# Sheet2.net
KiCad netlist of a schematic drawn in Altium Designer
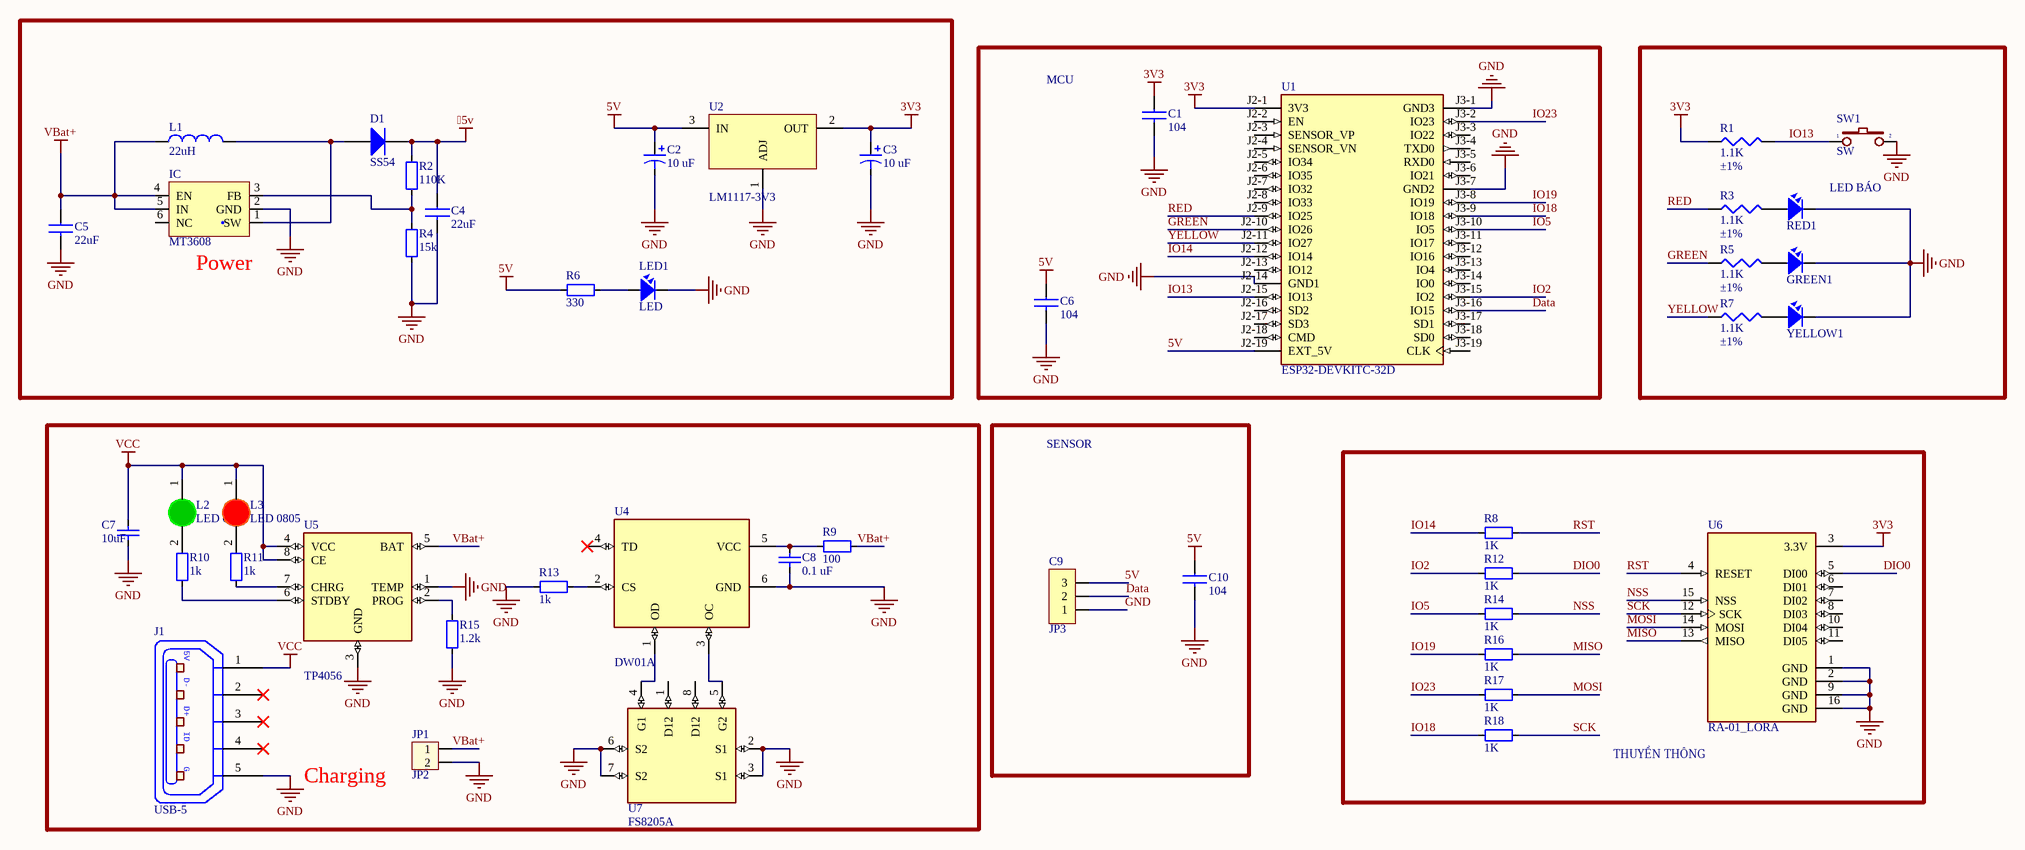
[diagram p0: Sheet2.SchDoc]

(export (version "E")
  (design (tool "Eeschema 10.0.6"))
  (components
    (comp (ref "C1")
      (value "104")
      (footprint "CAP0603")
      (description "CAP CER 30PF 50V NPO 0603")
      (fields
        (field (name "MANUFACTURER") "Yageo")
        (field (name "MANUFACTURER PART NUMBER") "CC0603JRNPO9BN300")
      )
      (libsource (lib "KhanhBK_SCH_Lib_6") (part "CC0603JRNPO9BN300"))
    )
    (comp (ref "C2")
      (value "10 uF")
      (footprint "C3MM")
      (description "Polarized Capacitor (Axial)")
      (fields (field (name "PUBLISHER") "Altium Limited"))
      (libsource (lib "My Library") (part "Cap Pol"))
    )
    (comp (ref "C3")
      (value "10 uF")
      (footprint "C3MM")
      (description "Polarized Capacitor (Axial)")
      (fields (field (name "PUBLISHER") "Altium Limited"))
      (libsource (lib "My Library") (part "Cap Pol"))
    )
    (comp (ref "C4")
      (value "22uF")
      (footprint "CAP0603")
      (description "CAP CER 30PF 50V NPO 0603")
      (fields
        (field (name "MANUFACTURER") "Yageo")
        (field (name "MANUFACTURER PART NUMBER") "CC0603JRNPO9BN300")
      )
      (libsource (lib "KhanhBK_SCH_Lib_6") (part "CC0603JRNPO9BN300"))
    )
    (comp (ref "C5")
      (value "22uF")
      (footprint "CAP0603")
      (description "CAP CER 30PF 50V NPO 0603")
      (fields
        (field (name "MANUFACTURER") "Yageo")
        (field (name "MANUFACTURER PART NUMBER") "CC0603JRNPO9BN300")
      )
      (libsource (lib "KhanhBK_SCH_Lib_6") (part "CC0603JRNPO9BN300"))
    )
    (comp (ref "C6")
      (value "104")
      (footprint "CAP0603")
      (description "CAP CER 30PF 50V NPO 0603")
      (fields
        (field (name "MANUFACTURER") "Yageo")
        (field (name "MANUFACTURER PART NUMBER") "CC0603JRNPO9BN300")
      )
      (libsource (lib "KhanhBK_SCH_Lib_6") (part "CC0603JRNPO9BN300"))
    )
    (comp (ref "C7")
      (value "10uF")
      (footprint "CAP_0805")
      (description "Capacitor")
      (fields (field (name "PUBLISHER") "Altium Limited"))
      (libsource (lib "My Library") (part "CapSMD"))
    )
    (comp (ref "C8")
      (value "0.1 uF")
      (footprint "CAP_0805")
      (description "Capacitor")
      (fields (field (name "PUBLISHER") "Altium Limited"))
      (libsource (lib "My Library") (part "CapSMD"))
    )
    (comp (ref "C9")
      (value "JP3")
      (footprint "JP3-C1T")
      (description "WR-PHD 2.54 mm Angled Socket Header")
      (fields
        (field (name "MANUFACTURER") "Würth Elektronik eiSos GmbH")
        (field (name "PARTNO") "613003143121")
        (field (name "CREATED BY") "Karrer Zheng")
      )
      (libsource (lib "KhanhBK_SCH_Library_1") (part "JP3"))
    )
    (comp (ref "C10")
      (value "104")
      (footprint "CAP0603")
      (description "CAP CER 30PF 50V NPO 0603")
      (fields
        (field (name "MANUFACTURER") "Yageo")
        (field (name "MANUFACTURER PART NUMBER") "CC0603JRNPO9BN300")
      )
      (libsource (lib "KhanhBK_SCH_Lib_6") (part "CC0603JRNPO9BN300"))
    )
    (comp (ref "D1")
      (value "SS54")
      (footprint "DIODE/POW/1A")
      (description "Diode Power")
      (fields (field (name "PUBLISHER") "Altium Limited"))
      (libsource (lib "Cty1") (part "Diode Power"))
    )
    (comp (ref "GREEN1")
      (value "LED")
      (footprint "LED-3MM-GREEN")
      (description "LED Single colour Green and Red")
      (libsource (lib "KhanhBK_SCH_Library_1") (part "LED"))
    )
    (comp (ref "IC") (value "MT3608") (footprint "TSOP 2") (libsource (lib "MT3608") (part "MT3608")))
    (comp (ref "J1")
      (value "USB-5")
      (footprint "USB-M1")
      (fields
        (field (name "MANUFACTURER") "FCI")
        (field (name "MANUFACTURER PART NUMBER") "10118193-0001LF")
        (field (name ".CREATOR") "MM")
        (field (name ".CHECKED PCB") "RF")
        (field (name ".CHECKED SCH") "MM")
      )
      (libsource (lib "My Library") (part "USB-5"))
    )
    (comp (ref "JP1")
      (value "JP2")
      (footprint "CON2")
      (description "Connector 2")
      (libsource (lib "My Library") (part "Con2"))
    )
    (comp (ref "L1")
      (value "22uH")
      (footprint "IND_400_500_212x114_SMD")
      (description "1mH Shielded Wirewound Inductor 600mA 1.82Ohm Max Nonstandard")
      (fields (field (name "MANUFACTURER") "Coilcraft") (field (name "MANUFACTURER PART NUMBER") "74477030"))
      (libsource (lib "Altium_Lib_by_KhueNguyenCreator") (part "IND_1mH-0.6A-20%-SMD"))
    )
    (comp (ref "L2")
      (value "LED 0805")
      (footprint "LED-0805-Green")
      (description "Dán")
      (libsource (lib "Altium_Lib_by_KhueNguyenCreator") (part "LED 0805 Xanh La"))
    )
    (comp (ref "L3")
      (value "LED 0805")
      (footprint "LED-0805-Red")
      (description "Dán")
      (libsource (lib "Altium_Lib_by_KhueNguyenCreator") (part "LED 0805 Do"))
    )
    (comp (ref "LED1")
      (value "LED")
      (footprint "LED-0805-Red")
      (description "LED Single colour Green and Red")
      (libsource (lib "My Library") (part "LED"))
    )
    (comp (ref "R1")
      (value "1.1K")
      (footprint "RES0603")
      (description "RES SMD 1K OHM 1% 1/10W 0603")
      (fields
        (field (name "MANUFACTURER") "Yageo")
        (field (name "MANUFACTURER PART NUMBER") "RT0603FRD071KL")
        (field (name "TOLERANCE") "±1%")
      )
      (libsource (lib "KhanhBK_SCH_Lib_6") (part "RT0603FRD071KL"))
    )
    (comp (ref "R2")
      (value "110K")
      (footprint "RES-SMD-0805")
      (description "Resistor")
      (fields
        (field (name "MANUFACTURER") "Generic Components")
        (field (name "PUBLISHER") "Altium Hobart Technology Centre")
      )
      (libsource (lib "My Library") (part "Resistor - SMD"))
    )
    (comp (ref "R3")
      (value "1.1K")
      (footprint "RES0603")
      (description "RES SMD 1K OHM 1% 1/10W 0603")
      (fields
        (field (name "MANUFACTURER") "Yageo")
        (field (name "MANUFACTURER PART NUMBER") "RT0603FRD071KL")
        (field (name "TOLERANCE") "±1%")
      )
      (libsource (lib "KhanhBK_SCH_Lib_6") (part "RT0603FRD071KL"))
    )
    (comp (ref "R4")
      (value "15k")
      (footprint "RES-SMD-0805")
      (description "Resistor")
      (fields
        (field (name "MANUFACTURER") "Generic Components")
        (field (name "PUBLISHER") "Altium Hobart Technology Centre")
      )
      (libsource (lib "My Library") (part "Resistor - SMD"))
    )
    (comp (ref "R5")
      (value "1.1K")
      (footprint "RES0603")
      (description "RES SMD 1K OHM 1% 1/10W 0603")
      (fields
        (field (name "MANUFACTURER") "Yageo")
        (field (name "MANUFACTURER PART NUMBER") "RT0603FRD071KL")
        (field (name "TOLERANCE") "±1%")
      )
      (libsource (lib "KhanhBK_SCH_Lib_6") (part "RT0603FRD071KL"))
    )
    (comp (ref "R6")
      (value "330")
      (footprint "RES-SMD-0805")
      (description "Resistor")
      (fields
        (field (name "MANUFACTURER") "Generic Components")
        (field (name "PUBLISHER") "Altium Hobart Technology Centre")
      )
      (libsource (lib "My Library") (part "Resistor - SMD"))
    )
    (comp (ref "R7")
      (value "1.1K")
      (footprint "RES0603")
      (description "RES SMD 1K OHM 1% 1/10W 0603")
      (fields
        (field (name "MANUFACTURER") "Yageo")
        (field (name "MANUFACTURER PART NUMBER") "RT0603FRD071KL")
        (field (name "TOLERANCE") "±1%")
      )
      (libsource (lib "KhanhBK_SCH_Lib_6") (part "RT0603FRD071KL"))
    )
    (comp (ref "R8")
      (value "1K")
      (footprint "RES-SMD-0805")
      (description "Resistor")
      (fields
        (field (name "MANUFACTURER") "Generic Components")
        (field (name "PUBLISHER") "Altium Hobart Technology Centre")
      )
      (libsource (lib "My Library") (part "Resistor - SMD"))
    )
    (comp (ref "R9")
      (value "100")
      (footprint "RES-SMD-0805")
      (description "Resistor")
      (fields
        (field (name "MANUFACTURER") "Generic Components")
        (field (name "PUBLISHER") "Altium Hobart Technology Centre")
      )
      (libsource (lib "My Library") (part "Resistor - SMD"))
    )
    (comp (ref "R10")
      (value "1k")
      (footprint "RES-SMD-0805")
      (description "Resistor")
      (fields
        (field (name "MANUFACTURER") "Generic Components")
        (field (name "PUBLISHER") "Altium Hobart Technology Centre")
      )
      (libsource (lib "My Library") (part "Resistor - SMD"))
    )
    (comp (ref "R11")
      (value "1k")
      (footprint "RES-SMD-0805")
      (description "Resistor")
      (fields
        (field (name "MANUFACTURER") "Generic Components")
        (field (name "PUBLISHER") "Altium Hobart Technology Centre")
      )
      (libsource (lib "My Library") (part "Resistor - SMD"))
    )
    (comp (ref "R12")
      (value "1K")
      (footprint "RES-SMD-0805")
      (description "Resistor")
      (fields
        (field (name "MANUFACTURER") "Generic Components")
        (field (name "PUBLISHER") "Altium Hobart Technology Centre")
      )
      (libsource (lib "My Library") (part "Resistor - SMD"))
    )
    (comp (ref "R13")
      (value "1k")
      (footprint "RES-SMD-0805")
      (description "Resistor")
      (fields
        (field (name "MANUFACTURER") "Generic Components")
        (field (name "PUBLISHER") "Altium Hobart Technology Centre")
      )
      (libsource (lib "My Library") (part "Resistor - SMD"))
    )
    (comp (ref "R14")
      (value "1K")
      (footprint "RES-SMD-0805")
      (description "Resistor")
      (fields
        (field (name "MANUFACTURER") "Generic Components")
        (field (name "PUBLISHER") "Altium Hobart Technology Centre")
      )
      (libsource (lib "My Library") (part "Resistor - SMD"))
    )
    (comp (ref "R15")
      (value "1.2k")
      (footprint "RES-SMD-0805")
      (description "Resistor")
      (fields
        (field (name "MANUFACTURER") "Generic Components")
        (field (name "PUBLISHER") "Altium Hobart Technology Centre")
      )
      (libsource (lib "My Library") (part "Resistor - SMD"))
    )
    (comp (ref "R16")
      (value "1K")
      (footprint "RES-SMD-0805")
      (description "Resistor")
      (fields
        (field (name "MANUFACTURER") "Generic Components")
        (field (name "PUBLISHER") "Altium Hobart Technology Centre")
      )
      (libsource (lib "My Library") (part "Resistor - SMD"))
    )
    (comp (ref "R17")
      (value "1K")
      (footprint "RES-SMD-0805")
      (description "Resistor")
      (fields
        (field (name "MANUFACTURER") "Generic Components")
        (field (name "PUBLISHER") "Altium Hobart Technology Centre")
      )
      (libsource (lib "My Library") (part "Resistor - SMD"))
    )
    (comp (ref "R18")
      (value "1K")
      (footprint "RES-SMD-0805")
      (description "Resistor")
      (fields
        (field (name "MANUFACTURER") "Generic Components")
        (field (name "PUBLISHER") "Altium Hobart Technology Centre")
      )
      (libsource (lib "My Library") (part "Resistor - SMD"))
    )
    (comp (ref "RED1")
      (value "LED")
      (footprint "LED-3MM-RED")
      (description "LED Single colour Green and Red")
      (libsource (lib "KhanhBK_SCH_Library_1") (part "LED"))
    )
    (comp (ref "SW1")
      (value "SW")
      (footprint "SW1-SMD")
      (description "Switch button 2 pin")
      (libsource (lib "KhanhBK_SCH_Library_1") (part "SW2"))
    )
    (comp (ref "U1")
      (value "ESP32-DEVKITC-32D")
      (footprint "MODULE_ESP32-DEVKITC-32D")
      (description "WiFi Development Tools (802.11) ESP32 General Development Kit, ESP32-WROOM-32D on the board")
      (fields (field (name "MF") "Espressif Systems"))
      (libsource (lib "ESP32-DEVKITC-32D") (part "ESP32-DEVKITC-32D"))
    )
    (comp (ref "U2")
      (value "LM1117-3V3")
      (footprint "LM1117-SOP")
      (description "800mA Low-Dropout Linear Regulator")
      (fields (field (name "CREATOR") "Nguyen Ba Bien"))
      (libsource (lib "My Library") (part "LM1117-ADJ"))
    )
    (comp (ref "U4")
      (value "DW01A")
      (footprint "SOT23-6")
      (description "One Cell Lithium-ion/Polymer Battery Protection IC")
      (libsource (lib "My Library") (part "DW01A"))
    )
    (comp (ref "U5")
      (value "TP4056")
      (footprint "TP4056")
      (description "Complete single cell Li-Ion battery with a constant current / constant voltage linear charger")
      (libsource (lib "My Library") (part "TP4056"))
    )
    (comp (ref "U6")
      (value "RA-01_LORA")
      (footprint "MODULE_RA-02_LORA")
      (description "Ra-02 LoRa RF M5Stack Platform Evaluation Expansion Board")
      (fields (field (name "MP") "RA-02_LORA"))
      (libsource (lib "RA-02_LORA (1)") (part "RA-02_LORA"))
    )
    (comp (ref "U7") (value "FS8205A") (footprint "FS8205A") (libsource (lib "My Library") (part "FS8205A")))
    (comp (ref "YELLOW1")
      (value "LED")
      (footprint "LED-3MM-YELLOW")
      (description "LED Single colour Green and Red")
      (libsource (lib "KhanhBK_SCH_Library_1") (part "LED"))
    )
  )
  (nets
    (net (code "1") (name "5v") (class "Default")
      (node (ref "C4") (pin "1") (pinfunction "1_1") (pintype "passive"))
      (node (ref "D1") (pin "2") (pinfunction "K_2") (pintype "passive"))
      (node (ref "R2") (pin "2") (pinfunction "2_2") (pintype "passive"))
    )
    (net (code "2") (name "/DIO0") (class "Default")
      (node (ref "R12") (pin "2") (pinfunction "2_2") (pintype "passive"))
      (node (ref "U6") (pin "5") (pinfunction "DI00_5") (pintype "bidirectional"))
    )
    (net (code "3") (name "/Data") (class "Default")
      (node (ref "C9") (pin "2") (pinfunction "2_2") (pintype "passive"))
      (node (ref "U1") (pin "J3-16") (pinfunction "IO15_J3-16") (pintype "bidirectional"))
    )
    (net (code "4") (name "/GREEN") (class "Default")
      (node (ref "R5") (pin "1") (pinfunction "1_1") (pintype "passive"))
      (node (ref "U1") (pin "J2-10") (pinfunction "IO26_J2-10") (pintype "bidirectional"))
    )
    (net (code "5") (name "/IO2") (class "Default")
      (node (ref "R12") (pin "1") (pinfunction "1_1") (pintype "passive"))
      (node (ref "U1") (pin "J3-15") (pinfunction "IO2_J3-15") (pintype "bidirectional"))
    )
    (net (code "6") (name "/IO5") (class "Default")
      (node (ref "R14") (pin "1") (pinfunction "1_1") (pintype "passive"))
      (node (ref "U1") (pin "J3-10") (pinfunction "IO5_J3-10") (pintype "bidirectional"))
    )
    (net (code "7") (name "/IO13") (class "Default")
      (node (ref "R1") (pin "2") (pinfunction "2_2") (pintype "passive"))
      (node (ref "SW1") (pin "1") (pinfunction "1_1") (pintype "passive"))
      (node (ref "U1") (pin "J2-15") (pinfunction "IO13_J2-15") (pintype "bidirectional"))
    )
    (net (code "8") (name "/IO14") (class "Default")
      (node (ref "R8") (pin "1") (pinfunction "1_1") (pintype "passive"))
      (node (ref "U1") (pin "J2-12") (pinfunction "IO14_J2-12") (pintype "bidirectional"))
    )
    (net (code "9") (name "/IO18") (class "Default")
      (node (ref "R18") (pin "1") (pinfunction "1_1") (pintype "passive"))
      (node (ref "U1") (pin "J3-9") (pinfunction "IO18_J3-9") (pintype "bidirectional"))
    )
    (net (code "10") (name "/IO19") (class "Default")
      (node (ref "R16") (pin "1") (pinfunction "1_1") (pintype "passive"))
      (node (ref "U1") (pin "J3-8") (pinfunction "IO19_J3-8") (pintype "bidirectional"))
    )
    (net (code "11") (name "/IO23") (class "Default")
      (node (ref "R17") (pin "1") (pinfunction "1_1") (pintype "passive"))
      (node (ref "U1") (pin "J3-2") (pinfunction "IO23_J3-2") (pintype "bidirectional"))
    )
    (net (code "12") (name "/MISO") (class "Default")
      (node (ref "R16") (pin "2") (pinfunction "2_2") (pintype "passive"))
      (node (ref "U6") (pin "13") (pinfunction "MISO_13") (pintype "output"))
    )
    (net (code "13") (name "/MOSI") (class "Default")
      (node (ref "R17") (pin "2") (pinfunction "2_2") (pintype "passive"))
      (node (ref "U6") (pin "14") (pinfunction "MOSI_14") (pintype "input"))
    )
    (net (code "14") (name "/NSS") (class "Default")
      (node (ref "R14") (pin "2") (pinfunction "2_2") (pintype "passive"))
      (node (ref "U6") (pin "15") (pinfunction "NSS_15") (pintype "input"))
    )
    (net (code "15") (name "/RED") (class "Default")
      (node (ref "R3") (pin "1") (pinfunction "1_1") (pintype "passive"))
      (node (ref "U1") (pin "J2-9") (pinfunction "IO25_J2-9") (pintype "bidirectional"))
    )
    (net (code "16") (name "/RST") (class "Default")
      (node (ref "R8") (pin "2") (pinfunction "2_2") (pintype "passive"))
      (node (ref "U6") (pin "4") (pinfunction "RESET_4") (pintype "input"))
    )
    (net (code "17") (name "/SCK") (class "Default")
      (node (ref "R18") (pin "2") (pinfunction "2_2") (pintype "passive"))
      (node (ref "U6") (pin "12") (pinfunction "SCK_12") (pintype "input"))
    )
    (net (code "18") (name "/YELLOW") (class "Default")
      (node (ref "R7") (pin "1") (pinfunction "1_1") (pintype "passive"))
      (node (ref "U1") (pin "J2-11") (pinfunction "IO27_J2-11") (pintype "bidirectional"))
    )
    (net (code "19") (name "3V3") (class "Default")
      (node (ref "C1") (pin "1") (pinfunction "1_1") (pintype "passive"))
      (node (ref "C3") (pin "1") (pinfunction "1_1") (pintype "passive"))
      (node (ref "R1") (pin "1") (pinfunction "1_1") (pintype "passive"))
      (node (ref "U1") (pin "J2-1") (pinfunction "3V3_J2-1") (pintype "power_in"))
      (node (ref "U2") (pin "2") (pinfunction "OUT_2") (pintype "passive"))
      (node (ref "U6") (pin "3") (pinfunction "3.3V_3") (pintype "power_in"))
    )
    (net (code "20") (name "5V") (class "Default")
      (node (ref "C10") (pin "1") (pinfunction "1_1") (pintype "passive"))
      (node (ref "C2") (pin "1") (pinfunction "1_1") (pintype "passive"))
      (node (ref "C6") (pin "1") (pinfunction "1_1") (pintype "passive"))
      (node (ref "C9") (pin "3") (pinfunction "3_3") (pintype "passive"))
      (node (ref "R6") (pin "1") (pinfunction "1_1") (pintype "passive"))
      (node (ref "U1") (pin "J2-19") (pinfunction "EXT_5V_J2-19") (pintype "power_in"))
      (node (ref "U2") (pin "3") (pinfunction "IN_3") (pintype "passive"))
    )
    (net (code "21") (name "GND") (class "Default")
      (node (ref "C1") (pin "2") (pinfunction "2_2") (pintype "passive"))
      (node (ref "C10") (pin "2") (pinfunction "2_2") (pintype "passive"))
      (node (ref "C2") (pin "2") (pinfunction "2_2") (pintype "passive"))
      (node (ref "C3") (pin "2") (pinfunction "2_2") (pintype "passive"))
      (node (ref "C4") (pin "2") (pinfunction "2_2") (pintype "passive"))
      (node (ref "C5") (pin "2") (pinfunction "2_2") (pintype "passive"))
      (node (ref "C6") (pin "2") (pinfunction "2_2") (pintype "passive"))
      (node (ref "C7") (pin "1") (pinfunction "1_1") (pintype "passive"))
      (node (ref "C8") (pin "1") (pinfunction "1_1") (pintype "passive"))
      (node (ref "C9") (pin "1") (pinfunction "1_1") (pintype "passive"))
      (node (ref "GREEN1") (pin "2") (pinfunction "2_2") (pintype "passive"))
      (node (ref "IC") (pin "2") (pinfunction "GND_2") (pintype "power_in"))
      (node (ref "J1") (pin "5") (pinfunction "P5_5") (pintype "passive"))
      (node (ref "JP1") (pin "2") (pinfunction "2_2") (pintype "passive"))
      (node (ref "LED1") (pin "2") (pinfunction "2_2") (pintype "passive"))
      (node (ref "R13") (pin "1") (pinfunction "1_1") (pintype "passive"))
      (node (ref "R15") (pin "1") (pinfunction "1_1") (pintype "passive"))
      (node (ref "R4") (pin "1") (pinfunction "1_1") (pintype "passive"))
      (node (ref "RED1") (pin "2") (pinfunction "2_2") (pintype "passive"))
      (node (ref "SW1") (pin "2") (pinfunction "2_2") (pintype "passive"))
      (node (ref "U1") (pin "J2-14") (pinfunction "GND1_J2-14") (pintype "power_in"))
      (node (ref "U1") (pin "J3-1") (pinfunction "GND3_J3-1") (pintype "power_in"))
      (node (ref "U1") (pin "J3-7") (pinfunction "GND2_J3-7") (pintype "power_in"))
      (node (ref "U2") (pin "1") (pinfunction "ADJ_1") (pintype "passive"))
      (node (ref "U4") (pin "6") (pinfunction "GND_6") (pintype "power_in"))
      (node (ref "U5") (pin "1") (pinfunction "TEMP_1") (pintype "bidirectional"))
      (node (ref "U5") (pin "3") (pinfunction "GND_3") (pintype "bidirectional"))
      (node (ref "U6") (pin "1") (pinfunction "GND_1") (pintype "power_in"))
      (node (ref "U6") (pin "16") (pinfunction "GND_16") (pintype "power_in"))
      (node (ref "U6") (pin "2") (pinfunction "GND_2") (pintype "power_in"))
      (node (ref "U6") (pin "9") (pinfunction "GND_9") (pintype "power_in"))
      (node (ref "U7") (pin "2") (pinfunction "S1_2") (pintype "bidirectional"))
      (node (ref "U7") (pin "3") (pinfunction "S1_3") (pintype "bidirectional"))
      (node (ref "U7") (pin "6") (pinfunction "S2_6") (pintype "bidirectional"))
      (node (ref "U7") (pin "7") (pinfunction "S2_7") (pintype "bidirectional"))
      (node (ref "YELLOW1") (pin "2") (pinfunction "2_2") (pintype "passive"))
    )
    (net (code "22") (name "Net-(D1-A)") (class "Default")
      (node (ref "D1") (pin "1") (pinfunction "A_1") (pintype "passive"))
      (node (ref "IC") (pin "1") (pinfunction "SW_1") (pintype "power_in"))
      (node (ref "L1") (pin "2") (pinfunction "2_2") (pintype "passive"))
    )
    (net (code "23") (name "Net-(GREEN1-Pad1)") (class "Default")
      (node (ref "GREEN1") (pin "1") (pinfunction "1_1") (pintype "passive"))
      (node (ref "R5") (pin "2") (pinfunction "2_2") (pintype "passive"))
    )
    (net (code "24") (name "Net-(IC-FB)") (class "Default")
      (node (ref "IC") (pin "3") (pinfunction "FB_3") (pintype "power_in"))
      (node (ref "R2") (pin "1") (pinfunction "1_1") (pintype "passive"))
      (node (ref "R4") (pin "2") (pinfunction "2_2") (pintype "passive"))
    )
    (net (code "25") (name "Net-(L2-K)") (class "Default")
      (node (ref "L2") (pin "2") (pinfunction "K_2") (pintype "passive"))
      (node (ref "R10") (pin "2") (pinfunction "2_2") (pintype "passive"))
    )
    (net (code "26") (name "Net-(L3-K)") (class "Default")
      (node (ref "L3") (pin "2") (pinfunction "K_2") (pintype "passive"))
      (node (ref "R11") (pin "2") (pinfunction "2_2") (pintype "passive"))
    )
    (net (code "27") (name "Net-(LED1-Pad1)") (class "Default")
      (node (ref "LED1") (pin "1") (pinfunction "1_1") (pintype "passive"))
      (node (ref "R6") (pin "2") (pinfunction "2_2") (pintype "passive"))
    )
    (net (code "28") (name "Net-(R3-Pad2)") (class "Default")
      (node (ref "R3") (pin "2") (pinfunction "2_2") (pintype "passive"))
      (node (ref "RED1") (pin "1") (pinfunction "1_1") (pintype "passive"))
    )
    (net (code "29") (name "Net-(R7-Pad2)") (class "Default")
      (node (ref "R7") (pin "2") (pinfunction "2_2") (pintype "passive"))
      (node (ref "YELLOW1") (pin "1") (pinfunction "1_1") (pintype "passive"))
    )
    (net (code "30") (name "Net-(U4-CS)") (class "Default")
      (node (ref "R13") (pin "2") (pinfunction "2_2") (pintype "passive"))
      (node (ref "U4") (pin "2") (pinfunction "CS_2") (pintype "bidirectional"))
    )
    (net (code "31") (name "Net-(U4-OC)") (class "Default")
      (node (ref "U4") (pin "3") (pinfunction "OC_3") (pintype "bidirectional"))
      (node (ref "U7") (pin "5") (pinfunction "G2_5") (pintype "bidirectional"))
    )
    (net (code "32") (name "Net-(U4-OD)") (class "Default")
      (node (ref "U4") (pin "1") (pinfunction "OD_1") (pintype "bidirectional"))
      (node (ref "U7") (pin "4") (pinfunction "G1_4") (pintype "bidirectional"))
    )
    (net (code "33") (name "Net-(U4-VCC)") (class "Default")
      (node (ref "C8") (pin "2") (pinfunction "2_2") (pintype "passive"))
      (node (ref "R9") (pin "1") (pinfunction "1_1") (pintype "passive"))
      (node (ref "U4") (pin "5") (pinfunction "VCC_5") (pintype "power_in"))
    )
    (net (code "34") (name "Net-(U5-CHRG)") (class "Default")
      (node (ref "R11") (pin "1") (pinfunction "1_1") (pintype "passive"))
      (node (ref "U5") (pin "7") (pinfunction "CHRG_7") (pintype "bidirectional"))
    )
    (net (code "35") (name "Net-(U5-PROG)") (class "Default")
      (node (ref "R15") (pin "2") (pinfunction "2_2") (pintype "passive"))
      (node (ref "U5") (pin "2") (pinfunction "PROG_2") (pintype "bidirectional"))
    )
    (net (code "36") (name "Net-(U5-STDBY)") (class "Default")
      (node (ref "R10") (pin "1") (pinfunction "1_1") (pintype "passive"))
      (node (ref "U5") (pin "6") (pinfunction "STDBY_6") (pintype "bidirectional"))
    )
    (net (code "37") (name "VBat+") (class "Default")
      (node (ref "C5") (pin "1") (pinfunction "1_1") (pintype "passive"))
      (node (ref "IC") (pin "4") (pinfunction "EN_4") (pintype "power_in"))
      (node (ref "IC") (pin "5") (pinfunction "IN_5") (pintype "power_in"))
      (node (ref "JP1") (pin "1") (pinfunction "1_1") (pintype "passive"))
      (node (ref "L1") (pin "1") (pinfunction "1_1") (pintype "passive"))
      (node (ref "R9") (pin "2") (pinfunction "2_2") (pintype "passive"))
      (node (ref "U5") (pin "5") (pinfunction "BAT_5") (pintype "bidirectional"))
    )
    (net (code "38") (name "VCC") (class "Default")
      (node (ref "C7") (pin "2") (pinfunction "2_2") (pintype "passive"))
      (node (ref "J1") (pin "1") (pinfunction "P1_1") (pintype "passive"))
      (node (ref "L2") (pin "1") (pinfunction "A_1") (pintype "passive"))
      (node (ref "L3") (pin "1") (pinfunction "A_1") (pintype "passive"))
      (node (ref "U5") (pin "4") (pinfunction "VCC_4") (pintype "bidirectional"))
      (node (ref "U5") (pin "8") (pinfunction "CE_8") (pintype "bidirectional"))
    )
    (net (code "39") (name "unconnected-(IC-NC-Pad6)") (class "Default")
      (node (ref "IC") (pin "6") (pinfunction "NC_6") (pintype "power_in"))
    )
    (net (code "40") (name "unconnected-(J1-P2-Pad2)") (class "Default")
      (node (ref "J1") (pin "2") (pinfunction "P2_2") (pintype "passive+no_connect"))
    )
    (net (code "41") (name "unconnected-(J1-P3-Pad3)") (class "Default")
      (node (ref "J1") (pin "3") (pinfunction "P3_3") (pintype "passive+no_connect"))
    )
    (net (code "42") (name "unconnected-(J1-P4-Pad4)") (class "Default")
      (node (ref "J1") (pin "4") (pinfunction "P4_4") (pintype "passive+no_connect"))
    )
    (net (code "43") (name "unconnected-(U1-CLK-PadJ3-19)") (class "Default")
      (node (ref "U1") (pin "J3-19") (pinfunction "CLK_J3-19") (pintype "input"))
    )
    (net (code "44") (name "unconnected-(U1-CMD-PadJ2-18)") (class "Default")
      (node (ref "U1") (pin "J2-18") (pinfunction "CMD_J2-18") (pintype "bidirectional"))
    )
    (net (code "45") (name "unconnected-(U1-EN-PadJ2-2)") (class "Default")
      (node (ref "U1") (pin "J2-2") (pinfunction "EN_J2-2") (pintype "input"))
    )
    (net (code "46") (name "unconnected-(U1-IO0-PadJ3-14)") (class "Default")
      (node (ref "U1") (pin "J3-14") (pinfunction "IO0_J3-14") (pintype "bidirectional"))
    )
    (net (code "47") (name "unconnected-(U1-IO4-PadJ3-13)") (class "Default")
      (node (ref "U1") (pin "J3-13") (pinfunction "IO4_J3-13") (pintype "bidirectional"))
    )
    (net (code "48") (name "unconnected-(U1-IO12-PadJ2-13)") (class "Default")
      (node (ref "U1") (pin "J2-13") (pinfunction "IO12_J2-13") (pintype "bidirectional"))
    )
    (net (code "49") (name "unconnected-(U1-IO16-PadJ3-12)") (class "Default")
      (node (ref "U1") (pin "J3-12") (pinfunction "IO16_J3-12") (pintype "bidirectional"))
    )
    (net (code "50") (name "unconnected-(U1-IO17-PadJ3-11)") (class "Default")
      (node (ref "U1") (pin "J3-11") (pinfunction "IO17_J3-11") (pintype "bidirectional"))
    )
    (net (code "51") (name "unconnected-(U1-IO21-PadJ3-6)") (class "Default")
      (node (ref "U1") (pin "J3-6") (pinfunction "IO21_J3-6") (pintype "bidirectional"))
    )
    (net (code "52") (name "unconnected-(U1-IO22-PadJ3-3)") (class "Default")
      (node (ref "U1") (pin "J3-3") (pinfunction "IO22_J3-3") (pintype "bidirectional"))
    )
    (net (code "53") (name "unconnected-(U1-IO32-PadJ2-7)") (class "Default")
      (node (ref "U1") (pin "J2-7") (pinfunction "IO32_J2-7") (pintype "bidirectional"))
    )
    (net (code "54") (name "unconnected-(U1-IO33-PadJ2-8)") (class "Default")
      (node (ref "U1") (pin "J2-8") (pinfunction "IO33_J2-8") (pintype "bidirectional"))
    )
    (net (code "55") (name "unconnected-(U1-IO34-PadJ2-5)") (class "Default")
      (node (ref "U1") (pin "J2-5") (pinfunction "IO34_J2-5") (pintype "bidirectional"))
    )
    (net (code "56") (name "unconnected-(U1-IO35-PadJ2-6)") (class "Default")
      (node (ref "U1") (pin "J2-6") (pinfunction "IO35_J2-6") (pintype "bidirectional"))
    )
    (net (code "57") (name "unconnected-(U1-RXD0-PadJ3-5)") (class "Default")
      (node (ref "U1") (pin "J3-5") (pinfunction "RXD0_J3-5") (pintype "input"))
    )
    (net (code "58") (name "unconnected-(U1-SD0-PadJ3-18)") (class "Default")
      (node (ref "U1") (pin "J3-18") (pinfunction "SD0_J3-18") (pintype "bidirectional"))
    )
    (net (code "59") (name "unconnected-(U1-SD1-PadJ3-17)") (class "Default")
      (node (ref "U1") (pin "J3-17") (pinfunction "SD1_J3-17") (pintype "bidirectional"))
    )
    (net (code "60") (name "unconnected-(U1-SD2-PadJ2-16)") (class "Default")
      (node (ref "U1") (pin "J2-16") (pinfunction "SD2_J2-16") (pintype "bidirectional"))
    )
    (net (code "61") (name "unconnected-(U1-SD3-PadJ2-17)") (class "Default")
      (node (ref "U1") (pin "J2-17") (pinfunction "SD3_J2-17") (pintype "bidirectional"))
    )
    (net (code "62") (name "unconnected-(U1-SENSOR_VN-PadJ2-4)") (class "Default")
      (node (ref "U1") (pin "J2-4") (pinfunction "SENSOR_VN_J2-4") (pintype "input"))
    )
    (net (code "63") (name "unconnected-(U1-SENSOR_VP-PadJ2-3)") (class "Default")
      (node (ref "U1") (pin "J2-3") (pinfunction "SENSOR_VP_J2-3") (pintype "input"))
    )
    (net (code "64") (name "unconnected-(U1-TXD0-PadJ3-4)") (class "Default")
      (node (ref "U1") (pin "J3-4") (pinfunction "TXD0_J3-4") (pintype "output"))
    )
    (net (code "65") (name "unconnected-(U4-TD-Pad4)") (class "Default")
      (node (ref "U4") (pin "4") (pinfunction "TD_4") (pintype "bidirectional+no_connect"))
    )
    (net (code "66") (name "unconnected-(U6-DI01-Pad6)") (class "Default")
      (node (ref "U6") (pin "6") (pinfunction "DI01_6") (pintype "bidirectional"))
    )
    (net (code "67") (name "unconnected-(U6-DI02-Pad7)") (class "Default")
      (node (ref "U6") (pin "7") (pinfunction "DI02_7") (pintype "bidirectional"))
    )
    (net (code "68") (name "unconnected-(U6-DI03-Pad8)") (class "Default")
      (node (ref "U6") (pin "8") (pinfunction "DI03_8") (pintype "bidirectional"))
    )
    (net (code "69") (name "unconnected-(U6-DI04-Pad10)") (class "Default")
      (node (ref "U6") (pin "10") (pinfunction "DI04_10") (pintype "bidirectional"))
    )
    (net (code "70") (name "unconnected-(U6-DI05-Pad11)") (class "Default")
      (node (ref "U6") (pin "11") (pinfunction "DI05_11") (pintype "bidirectional"))
    )
    (net (code "71") (name "unconnected-(U7-D12-Pad1)") (class "Default")
      (node (ref "U7") (pin "1") (pinfunction "D12_1") (pintype "bidirectional"))
    )
    (net (code "72") (name "unconnected-(U7-D12-Pad8)") (class "Default")
      (node (ref "U7") (pin "8") (pinfunction "D12_8") (pintype "bidirectional"))
    )
  )
)
